# carrier1.net
KiCad netlist of a schematic drawn in EAGLE
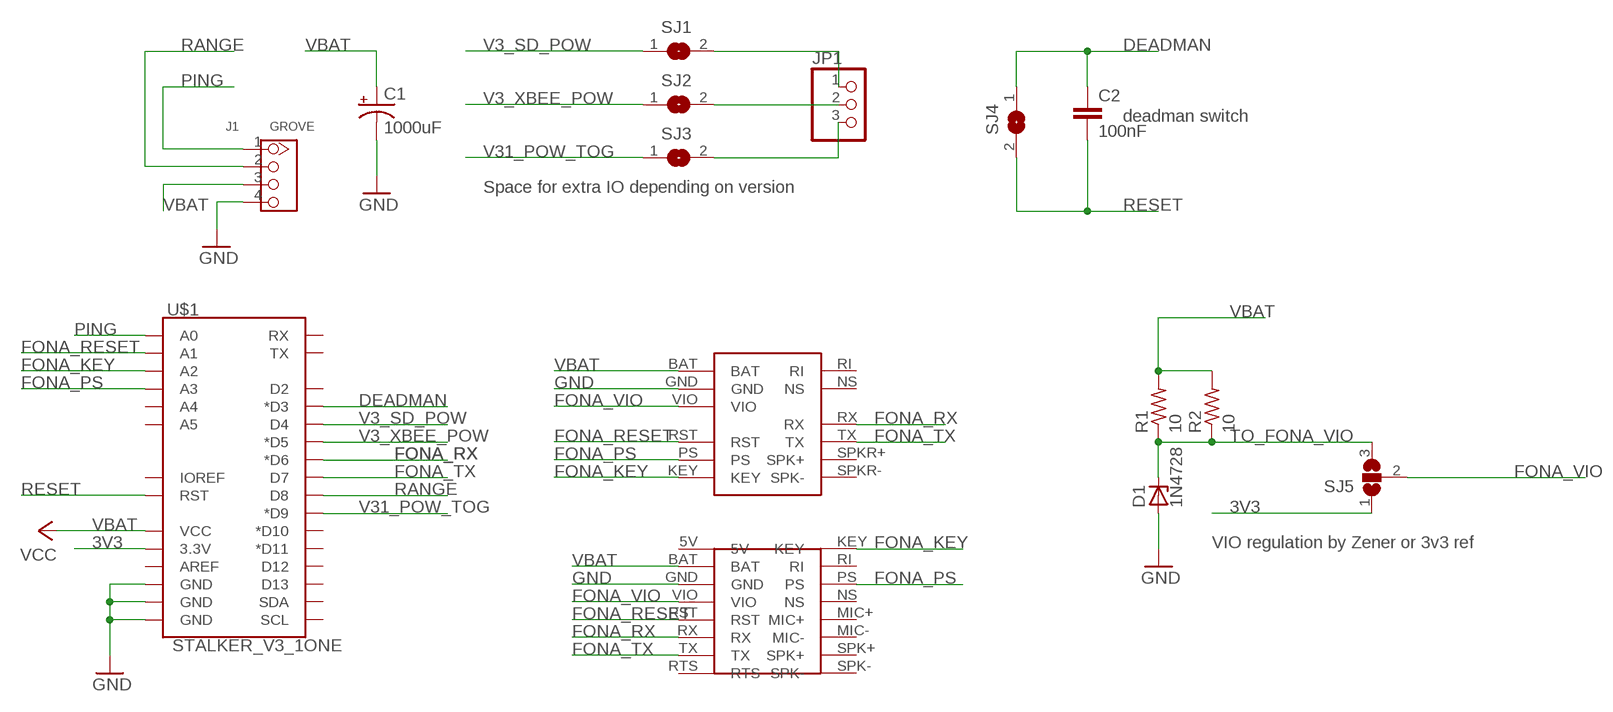
[diagram p0: schematic, sheet 1]

(export (version "E")
  (design (tool "Eeschema 10.0.6"))
  (components
    (comp (ref "C1")
      (value "1000uF")
      (footprint "eagle-import:E3,5-8")
      (libsource (lib "eagle-import") (part "CPOL-USE3.5-8"))
    )
    (comp (ref "C2")
      (value "100nF")
      (footprint "eagle-import:C0805")
      (libsource (lib "eagle-import") (part "C-EUC0805"))
    )
    (comp (ref "D1")
      (value "1N4728")
      (footprint "eagle-import:DO41Z10")
      (libsource (lib "eagle-import") (part "1N4728"))
    )
    (comp (ref "J1")
      (value "GROVE")
      (footprint "eagle-import:HW4-2.0")
      (libsource (lib "eagle-import") (part "GROVE-CONNECTOR-DIP(4P-2.0)"))
    )
    (comp (ref "JP1")
      (value "PINHD-1X3")
      (footprint "eagle-import:1X03")
      (libsource (lib "eagle-import") (part "PINHD-1X3"))
    )
    (comp (ref "R1")
      (value "10")
      (footprint "eagle-import:R0805")
      (libsource (lib "eagle-import") (part "R-US_R0805"))
    )
    (comp (ref "R2")
      (value "10")
      (footprint "eagle-import:0207_10")
      (libsource (lib "eagle-import") (part "R-US_0207/10"))
    )
    (comp (ref "SJ1") (value "SJ") (footprint "eagle-import:SJ") (libsource (lib "eagle-import") (part "SJ")))
    (comp (ref "SJ2") (value "SJ") (footprint "eagle-import:SJ") (libsource (lib "eagle-import") (part "SJ")))
    (comp (ref "SJ3") (value "SJ") (footprint "eagle-import:SJ") (libsource (lib "eagle-import") (part "SJ")))
    (comp (ref "SJ4") (value "SJ") (footprint "eagle-import:SJ") (libsource (lib "eagle-import") (part "SJ")))
    (comp (ref "SJ5")
      (value "SJ2W")
      (footprint "eagle-import:SJ_2")
      (libsource (lib "eagle-import") (part "SJ2W"))
    )
    (comp (ref "U$1")
      (value "STALKER_V3_1ONE")
      (footprint "eagle-import:STALKER_V3_1_PACKAGE")
      (libsource (lib "eagle-import") (part "STALKER_V3_1ONE"))
    )
    (comp (ref "U$2")
      (value "FONA_800_BREAKOUTONE")
      (footprint "eagle-import:FONA_800_H_L_BREAKOUT")
      (libsource (lib "eagle-import") (part "FONA_800_BREAKOUTONE"))
    )
    (comp (ref "U$3")
      (value "FONA_808_BREAKOUTONE")
      (footprint "eagle-import:FONA_808_BREAKOUT")
      (libsource (lib "eagle-import") (part "FONA_808_BREAKOUTONE"))
    )
  )
  (nets
    (net (code "1") (name "/3V3") (class "Default")
      (node (ref "SJ5") (pin "1") (pinfunction "1_1") (pintype "passive"))
      (node (ref "U$1") (pin "3.3V") (pinfunction "3.3V_3.3V") (pintype "bidirectional"))
    )
    (net (code "2") (name "/5V") (class "Default")
      (node (ref "U$3") (pin "5V") (pinfunction "5V_5V") (pintype "power_in"))
    )
    (net (code "3") (name "/DEADMAN") (class "Default")
      (node (ref "C2") (pin "1") (pinfunction "1_1") (pintype "passive"))
      (node (ref "SJ4") (pin "1") (pinfunction "1_1") (pintype "passive"))
      (node (ref "U$1") (pin "D3") (pinfunction "*D3_D3") (pintype "bidirectional"))
    )
    (net (code "4") (name "/FONA_KEY") (class "Default")
      (node (ref "U$1") (pin "A2") (pinfunction "A2_A2") (pintype "bidirectional"))
      (node (ref "U$2") (pin "KEY") (pinfunction "KEY_KEY") (pintype "bidirectional"))
      (node (ref "U$3") (pin "KEY") (pinfunction "KEY_KEY") (pintype "bidirectional"))
    )
    (net (code "5") (name "/FONA_PS") (class "Default")
      (node (ref "U$1") (pin "A3") (pinfunction "A3_A3") (pintype "bidirectional"))
      (node (ref "U$2") (pin "PS") (pinfunction "PS_PS") (pintype "bidirectional"))
      (node (ref "U$3") (pin "PS") (pinfunction "PS_PS") (pintype "bidirectional"))
    )
    (net (code "6") (name "/FONA_RESET") (class "Default")
      (node (ref "U$1") (pin "A1") (pinfunction "A1_A1") (pintype "bidirectional"))
      (node (ref "U$2") (pin "RST") (pinfunction "RST_RST") (pintype "bidirectional"))
      (node (ref "U$3") (pin "RST") (pinfunction "RST_RST") (pintype "bidirectional"))
    )
    (net (code "7") (name "/FONA_RX") (class "Default")
      (node (ref "U$1") (pin "D6") (pinfunction "*D6_D6") (pintype "bidirectional"))
      (node (ref "U$2") (pin "RX") (pinfunction "RX_RX") (pintype "bidirectional"))
      (node (ref "U$3") (pin "RX") (pinfunction "RX_RX") (pintype "bidirectional"))
    )
    (net (code "8") (name "/FONA_TX") (class "Default")
      (node (ref "U$1") (pin "D7") (pinfunction "D7_D7") (pintype "bidirectional"))
      (node (ref "U$2") (pin "TX") (pinfunction "TX_TX") (pintype "bidirectional"))
      (node (ref "U$3") (pin "TX") (pinfunction "TX_TX") (pintype "bidirectional"))
    )
    (net (code "9") (name "/FONA_VIO") (class "Default")
      (node (ref "SJ5") (pin "2") (pinfunction "2_2") (pintype "passive"))
      (node (ref "U$2") (pin "VIO") (pinfunction "VIO_VIO") (pintype "bidirectional"))
      (node (ref "U$3") (pin "VIO") (pinfunction "VIO_VIO") (pintype "bidirectional"))
    )
    (net (code "10") (name "/PING") (class "Default")
      (node (ref "J1") (pin "1") (pinfunction "1_1") (pintype "bidirectional"))
      (node (ref "U$1") (pin "A0") (pinfunction "A0_A0") (pintype "bidirectional"))
    )
    (net (code "11") (name "/RANGE") (class "Default")
      (node (ref "J1") (pin "2") (pinfunction "2_2") (pintype "bidirectional"))
      (node (ref "U$1") (pin "D8") (pinfunction "D8_D8") (pintype "bidirectional"))
    )
    (net (code "12") (name "/RESET") (class "Default")
      (node (ref "C2") (pin "2") (pinfunction "2_2") (pintype "passive"))
      (node (ref "SJ4") (pin "2") (pinfunction "2_2") (pintype "passive"))
      (node (ref "U$1") (pin "RES") (pinfunction "RST_RES") (pintype "bidirectional"))
    )
    (net (code "13") (name "/TO_FONA_VIO") (class "Default")
      (node (ref "D1") (pin "C") (pinfunction "C_C") (pintype "passive"))
      (node (ref "R1") (pin "1") (pinfunction "1_1") (pintype "passive"))
      (node (ref "R2") (pin "1") (pinfunction "1_1") (pintype "passive"))
      (node (ref "SJ5") (pin "3") (pinfunction "3_3") (pintype "passive"))
    )
    (net (code "14") (name "/V3_SD_POW") (class "Default")
      (node (ref "SJ1") (pin "1") (pinfunction "1_1") (pintype "passive"))
      (node (ref "U$1") (pin "D4") (pinfunction "D4_D4") (pintype "bidirectional"))
    )
    (net (code "15") (name "/V3_XBEE_POW") (class "Default")
      (node (ref "SJ2") (pin "1") (pinfunction "1_1") (pintype "passive"))
      (node (ref "U$1") (pin "D5") (pinfunction "*D5_D5") (pintype "bidirectional"))
    )
    (net (code "16") (name "/V31_POW_TOG") (class "Default")
      (node (ref "SJ3") (pin "1") (pinfunction "1_1") (pintype "passive"))
      (node (ref "U$1") (pin "D9") (pinfunction "*D9_D9") (pintype "bidirectional"))
    )
    (net (code "17") (name "GND") (class "Default")
      (node (ref "C1") (pin "-") (pinfunction "-_-") (pintype "passive"))
      (node (ref "D1") (pin "A") (pinfunction "A_A") (pintype "passive"))
      (node (ref "J1") (pin "4") (pinfunction "4_4") (pintype "bidirectional"))
      (node (ref "U$1") (pin "GND@0") (pinfunction "GND_GND@0") (pintype "power_in"))
      (node (ref "U$1") (pin "GND@1") (pinfunction "GND_GND@1") (pintype "power_in"))
      (node (ref "U$1") (pin "GND@2") (pinfunction "GND_GND@2") (pintype "power_in"))
      (node (ref "U$2") (pin "GND") (pinfunction "GND_GND") (pintype "power_in"))
      (node (ref "U$3") (pin "GND") (pinfunction "GND_GND") (pintype "power_in"))
    )
    (net (code "18") (name "Net-(JP1-Pad1)") (class "Default")
      (node (ref "JP1") (pin "1") (pinfunction "1_1") (pintype "passive"))
      (node (ref "SJ1") (pin "2") (pinfunction "2_2") (pintype "passive"))
    )
    (net (code "19") (name "Net-(JP1-Pad2)") (class "Default")
      (node (ref "JP1") (pin "2") (pinfunction "2_2") (pintype "passive"))
      (node (ref "SJ2") (pin "2") (pinfunction "2_2") (pintype "passive"))
    )
    (net (code "20") (name "Net-(JP1-Pad3)") (class "Default")
      (node (ref "JP1") (pin "3") (pinfunction "3_3") (pintype "passive"))
      (node (ref "SJ3") (pin "2") (pinfunction "2_2") (pintype "passive"))
    )
    (net (code "21") (name "VCC") (class "Default")
      (node (ref "C1") (pin "+") (pinfunction "+_+") (pintype "passive"))
      (node (ref "J1") (pin "3") (pinfunction "3_3") (pintype "bidirectional"))
      (node (ref "R1") (pin "2") (pinfunction "2_2") (pintype "passive"))
      (node (ref "R2") (pin "2") (pinfunction "2_2") (pintype "passive"))
      (node (ref "U$1") (pin "VCC") (pinfunction "VCC_VCC") (pintype "power_in"))
      (node (ref "U$2") (pin "BAT") (pinfunction "BAT_BAT") (pintype "power_in"))
      (node (ref "U$3") (pin "BAT") (pinfunction "BAT_BAT") (pintype "power_in"))
    )
    (net (code "22") (name "unconnected-(U$1-*D10-PadD10)") (class "Default")
      (node (ref "U$1") (pin "D10") (pinfunction "*D10_D10") (pintype "bidirectional"))
    )
    (net (code "23") (name "unconnected-(U$1-*D11-PadD11)") (class "Default")
      (node (ref "U$1") (pin "D11") (pinfunction "*D11_D11") (pintype "bidirectional"))
    )
    (net (code "24") (name "unconnected-(U$1-PadA4)") (class "Default")
      (node (ref "U$1") (pin "A4") (pinfunction "A4_A4") (pintype "bidirectional"))
    )
    (net (code "25") (name "unconnected-(U$1-PadA5)") (class "Default")
      (node (ref "U$1") (pin "A5") (pinfunction "A5_A5") (pintype "bidirectional"))
    )
    (net (code "26") (name "unconnected-(U$1-PadAREF)") (class "Default")
      (node (ref "U$1") (pin "AREF") (pinfunction "AREF_AREF") (pintype "bidirectional"))
    )
    (net (code "27") (name "unconnected-(U$1-PadD2)") (class "Default")
      (node (ref "U$1") (pin "D2") (pinfunction "D2_D2") (pintype "bidirectional"))
    )
    (net (code "28") (name "unconnected-(U$1-PadD12)") (class "Default")
      (node (ref "U$1") (pin "D12") (pinfunction "D12_D12") (pintype "bidirectional"))
    )
    (net (code "29") (name "unconnected-(U$1-PadD13)") (class "Default")
      (node (ref "U$1") (pin "D13") (pinfunction "D13_D13") (pintype "bidirectional"))
    )
    (net (code "30") (name "unconnected-(U$1-PadIOREF)") (class "Default")
      (node (ref "U$1") (pin "IOREF") (pinfunction "IOREF_IOREF") (pintype "bidirectional"))
    )
    (net (code "31") (name "unconnected-(U$1-PadRX)") (class "Default")
      (node (ref "U$1") (pin "RX") (pinfunction "RX_RX") (pintype "bidirectional"))
    )
    (net (code "32") (name "unconnected-(U$1-PadSCL)") (class "Default")
      (node (ref "U$1") (pin "SCL") (pinfunction "SCL_SCL") (pintype "bidirectional"))
    )
    (net (code "33") (name "unconnected-(U$1-PadSDA)") (class "Default")
      (node (ref "U$1") (pin "SDA") (pinfunction "SDA_SDA") (pintype "bidirectional"))
    )
    (net (code "34") (name "unconnected-(U$1-PadTX)") (class "Default")
      (node (ref "U$1") (pin "TX") (pinfunction "TX_TX") (pintype "bidirectional"))
    )
    (net (code "35") (name "unconnected-(U$2-PadNS)") (class "Default")
      (node (ref "U$2") (pin "NS") (pinfunction "NS_NS") (pintype "bidirectional"))
    )
    (net (code "36") (name "unconnected-(U$2-PadRI)") (class "Default")
      (node (ref "U$2") (pin "RI") (pinfunction "RI_RI") (pintype "bidirectional"))
    )
    (net (code "37") (name "unconnected-(U$2-SPK+-PadSPKR+)") (class "Default")
      (node (ref "U$2") (pin "SPKR+") (pinfunction "SPK+_SPKR+") (pintype "bidirectional"))
    )
    (net (code "38") (name "unconnected-(U$2-SPK--PadSPKR-)") (class "Default")
      (node (ref "U$2") (pin "SPKR-") (pinfunction "SPK-_SPKR-") (pintype "bidirectional"))
    )
    (net (code "39") (name "unconnected-(U$3-PadMIC+)") (class "Default")
      (node (ref "U$3") (pin "MIC+") (pinfunction "MIC+_MIC+") (pintype "bidirectional"))
    )
    (net (code "40") (name "unconnected-(U$3-PadMIC-)") (class "Default")
      (node (ref "U$3") (pin "MIC-") (pinfunction "MIC-_MIC-") (pintype "bidirectional"))
    )
    (net (code "41") (name "unconnected-(U$3-PadNS)") (class "Default")
      (node (ref "U$3") (pin "NS") (pinfunction "NS_NS") (pintype "bidirectional"))
    )
    (net (code "42") (name "unconnected-(U$3-PadRI)") (class "Default")
      (node (ref "U$3") (pin "RI") (pinfunction "RI_RI") (pintype "bidirectional"))
    )
    (net (code "43") (name "unconnected-(U$3-PadRTS)") (class "Default")
      (node (ref "U$3") (pin "RTS") (pinfunction "RTS_RTS") (pintype "bidirectional"))
    )
    (net (code "44") (name "unconnected-(U$3-PadSPK+)") (class "Default")
      (node (ref "U$3") (pin "SPK+") (pinfunction "SPK+_SPK+") (pintype "bidirectional"))
    )
    (net (code "45") (name "unconnected-(U$3-PadSPK-)") (class "Default")
      (node (ref "U$3") (pin "SPK-") (pinfunction "SPK-_SPK-") (pintype "bidirectional"))
    )
  )
)
